# RS-485.net
KiCad netlist of a schematic drawn in Altium Designer
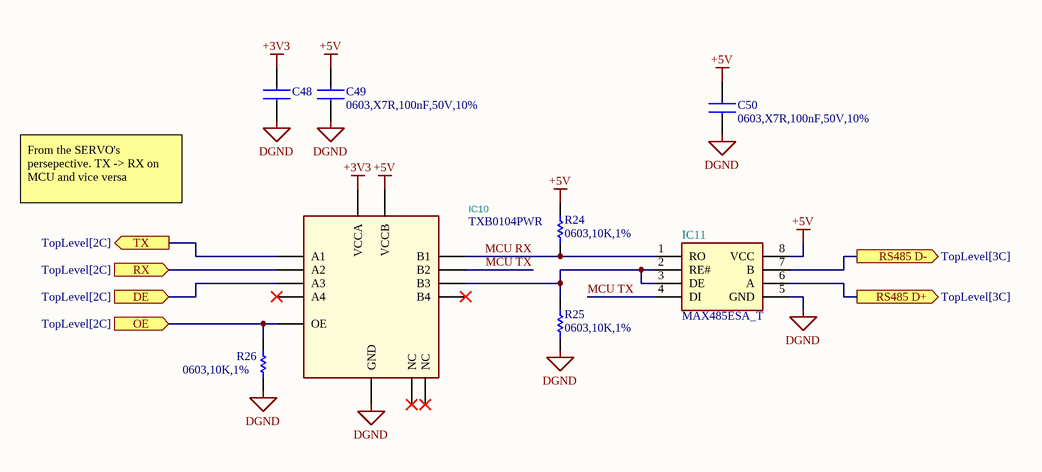
[diagram p0: RS-485.SchDoc]

(export (version "E")
  (design (tool "Eeschema 10.0.6"))
  (components
    (comp (ref "C48")
      (value "0603,X7R,100nF,50V,10%")
      (footprint "CAPC1608X90N")
      (description "50V 100nF X7R ±10% 0603 Multilayer Ceramic Capacitors MLCC - SMD/SMT ROHS")
      (fields (field (name "LCSC PART #") "C14663") (field (name "MANU PART #") "CC0603KRX7R9BB104"))
      (libsource (lib "flight-controller") (part "CC0603KRX7R9BB104"))
    )
    (comp (ref "C49")
      (value "0603,X7R,100nF,50V,10%")
      (footprint "CAPC1608X90N")
      (description "50V 100nF X7R ±10% 0603 Multilayer Ceramic Capacitors MLCC - SMD/SMT ROHS")
      (fields (field (name "LCSC PART #") "C14663") (field (name "MANU PART #") "CC0603KRX7R9BB104"))
      (libsource (lib "flight-controller") (part "CC0603KRX7R9BB104"))
    )
    (comp (ref "C50")
      (value "0603,X7R,100nF,50V,10%")
      (footprint "CAPC1608X90N")
      (description "50V 100nF X7R ±10% 0603 Multilayer Ceramic Capacitors MLCC - SMD/SMT ROHS")
      (fields (field (name "LCSC PART #") "C14663") (field (name "MANU PART #") "CC0603KRX7R9BB104"))
      (libsource (lib "flight-controller") (part "CC0603KRX7R9BB104"))
    )
    (comp (ref "IC10")
      (value "TXB0104PWR")
      (footprint "TXB0104PWR")
      (fields (field (name "MANUFACTURER") "Texas Instruments") (field (name "LCSC PART #") "C60708"))
      (libsource (lib "flight-controller") (part "TXB0104PWR"))
    )
    (comp (ref "IC11")
      (value "MAX485ESA_T")
      (footprint "MAX485ESA_T")
      (description "-40℃~+85℃ 1 1 2.5Mbps 4.75V~5.25V Transceiver SOIC-8 RS-485 / RS-422 ICs ROHS")
      (fields (field (name "LCSC PART #") "C19738") (field (name "MANU PART #") "MAX485ESA+T"))
      (libsource (lib "flight-controller") (part "MAX485ESA_T"))
    )
    (comp (ref "R24")
      (value "0603,10K,1%")
      (footprint "RESC1608X55N")
      (description "100mW Thick Film Resistor 75V ±100ppm/℃ ±1% 10kΩ 0603 Chip Resistor - Surface Mount ROHS")
      (fields (field (name "LCSC PART #") "C98220") (field (name "MANU PART #") "RC0603FR-0710KL"))
      (libsource (lib "flight-controller") (part "RC0603FR-0710KL"))
    )
    (comp (ref "R25")
      (value "0603,10K,1%")
      (footprint "RESC1608X55N")
      (description "100mW Thick Film Resistor 75V ±100ppm/℃ ±1% 10kΩ 0603 Chip Resistor - Surface Mount ROHS")
      (fields (field (name "LCSC PART #") "C98220") (field (name "MANU PART #") "RC0603FR-0710KL"))
      (libsource (lib "flight-controller") (part "RC0603FR-0710KL"))
    )
    (comp (ref "R26")
      (value "0603,10K,1%")
      (footprint "RESC1608X55N")
      (description "100mW Thick Film Resistor 75V ±100ppm/℃ ±1% 10kΩ 0603 Chip Resistor - Surface Mount ROHS")
      (fields (field (name "LCSC PART #") "C98220") (field (name "MANU PART #") "RC0603FR-0710KL"))
      (libsource (lib "flight-controller") (part "RC0603FR-0710KL"))
    )
  )
  (nets
    (net (code "1") (name "+3V3") (class "Default")
      (node (ref "C48") (pin "2") (pinfunction "2_2") (pintype "passive"))
      (node (ref "IC10") (pin "1") (pinfunction "VCCA_1") (pintype "passive"))
    )
    (net (code "2") (name "+5V") (class "Default")
      (node (ref "C49") (pin "2") (pinfunction "2_2") (pintype "passive"))
      (node (ref "C50") (pin "2") (pinfunction "2_2") (pintype "passive"))
      (node (ref "IC10") (pin "14") (pinfunction "VCCB_14") (pintype "passive"))
      (node (ref "IC11") (pin "8") (pinfunction "VCC_8") (pintype "passive"))
      (node (ref "R24") (pin "2") (pinfunction "2_2") (pintype "passive"))
    )
    (net (code "3") (name "/DE") (class "Default")
      (node (ref "IC10") (pin "4") (pinfunction "A3_4") (pintype "passive"))
    )
    (net (code "4") (name "/MCU RX") (class "Default")
      (node (ref "IC10") (pin "13") (pinfunction "B1_13") (pintype "passive"))
      (node (ref "IC11") (pin "1") (pinfunction "RO_1") (pintype "passive"))
      (node (ref "R24") (pin "1") (pinfunction "1_1") (pintype "passive"))
    )
    (net (code "5") (name "/MCU TX") (class "Default")
      (node (ref "IC10") (pin "12") (pinfunction "B2_12") (pintype "passive"))
      (node (ref "IC11") (pin "4") (pinfunction "DI_4") (pintype "passive"))
    )
    (net (code "6") (name "/OE") (class "Default")
      (node (ref "IC10") (pin "8") (pinfunction "OE_8") (pintype "passive"))
      (node (ref "R26") (pin "2") (pinfunction "2_2") (pintype "passive"))
    )
    (net (code "7") (name "/RS485 D+") (class "Default")
      (node (ref "IC11") (pin "6") (pinfunction "A_6") (pintype "passive"))
    )
    (net (code "8") (name "/RS485 D-") (class "Default")
      (node (ref "IC11") (pin "7") (pinfunction "B_7") (pintype "passive"))
    )
    (net (code "9") (name "/RX") (class "Default")
      (node (ref "IC10") (pin "3") (pinfunction "A2_3") (pintype "passive"))
    )
    (net (code "10") (name "/TX") (class "Default")
      (node (ref "IC10") (pin "2") (pinfunction "A1_2") (pintype "passive"))
    )
    (net (code "11") (name "DGND") (class "Default")
      (node (ref "C48") (pin "1") (pinfunction "1_1") (pintype "passive"))
      (node (ref "C49") (pin "1") (pinfunction "1_1") (pintype "passive"))
      (node (ref "C50") (pin "1") (pinfunction "1_1") (pintype "passive"))
      (node (ref "IC10") (pin "7") (pinfunction "GND_7") (pintype "passive"))
      (node (ref "IC11") (pin "5") (pinfunction "GND_5") (pintype "passive"))
      (node (ref "R25") (pin "1") (pinfunction "1_1") (pintype "passive"))
      (node (ref "R26") (pin "1") (pinfunction "1_1") (pintype "passive"))
    )
    (net (code "12") (name "Net-(IC10-B3)") (class "Default")
      (node (ref "IC10") (pin "11") (pinfunction "B3_11") (pintype "passive"))
      (node (ref "IC11") (pin "2") (pinfunction "RE#_2") (pintype "passive"))
      (node (ref "IC11") (pin "3") (pinfunction "DE_3") (pintype "passive"))
      (node (ref "R25") (pin "2") (pinfunction "2_2") (pintype "passive"))
    )
    (net (code "13") (name "unconnected-(IC10-A4-Pad5)") (class "Default")
      (node (ref "IC10") (pin "5") (pinfunction "A4_5") (pintype "passive+no_connect"))
    )
    (net (code "14") (name "unconnected-(IC10-B4-Pad10)") (class "Default")
      (node (ref "IC10") (pin "10") (pinfunction "B4_10") (pintype "passive+no_connect"))
    )
    (net (code "15") (name "unconnected-(IC10-NC-Pad6)") (class "Default")
      (node (ref "IC10") (pin "6") (pinfunction "NC_6") (pintype "passive+no_connect"))
    )
    (net (code "16") (name "unconnected-(IC10-NC-Pad9)") (class "Default")
      (node (ref "IC10") (pin "9") (pinfunction "NC_9") (pintype "passive+no_connect"))
    )
  )
)
